# KGGR_wD.net
KiCad netlist of a schematic drawn in EAGLE
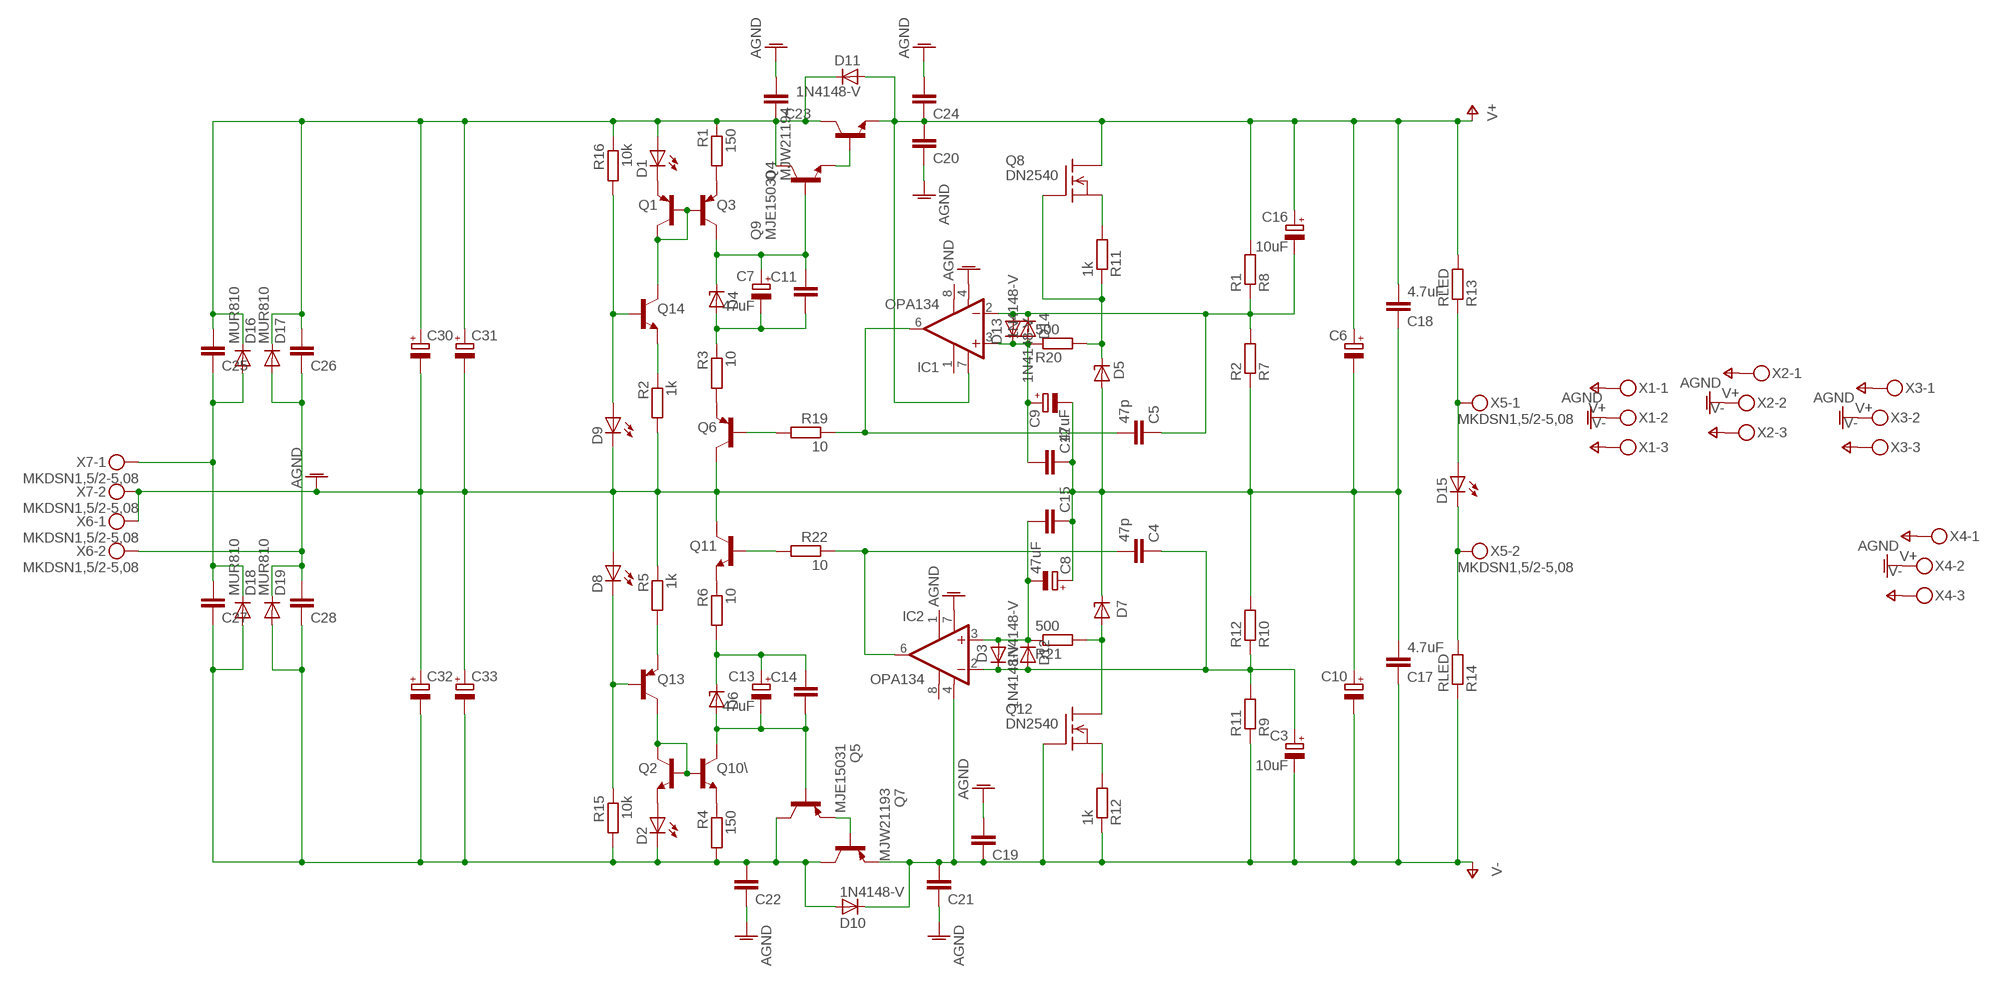
[diagram p0: schematic, sheet 1]
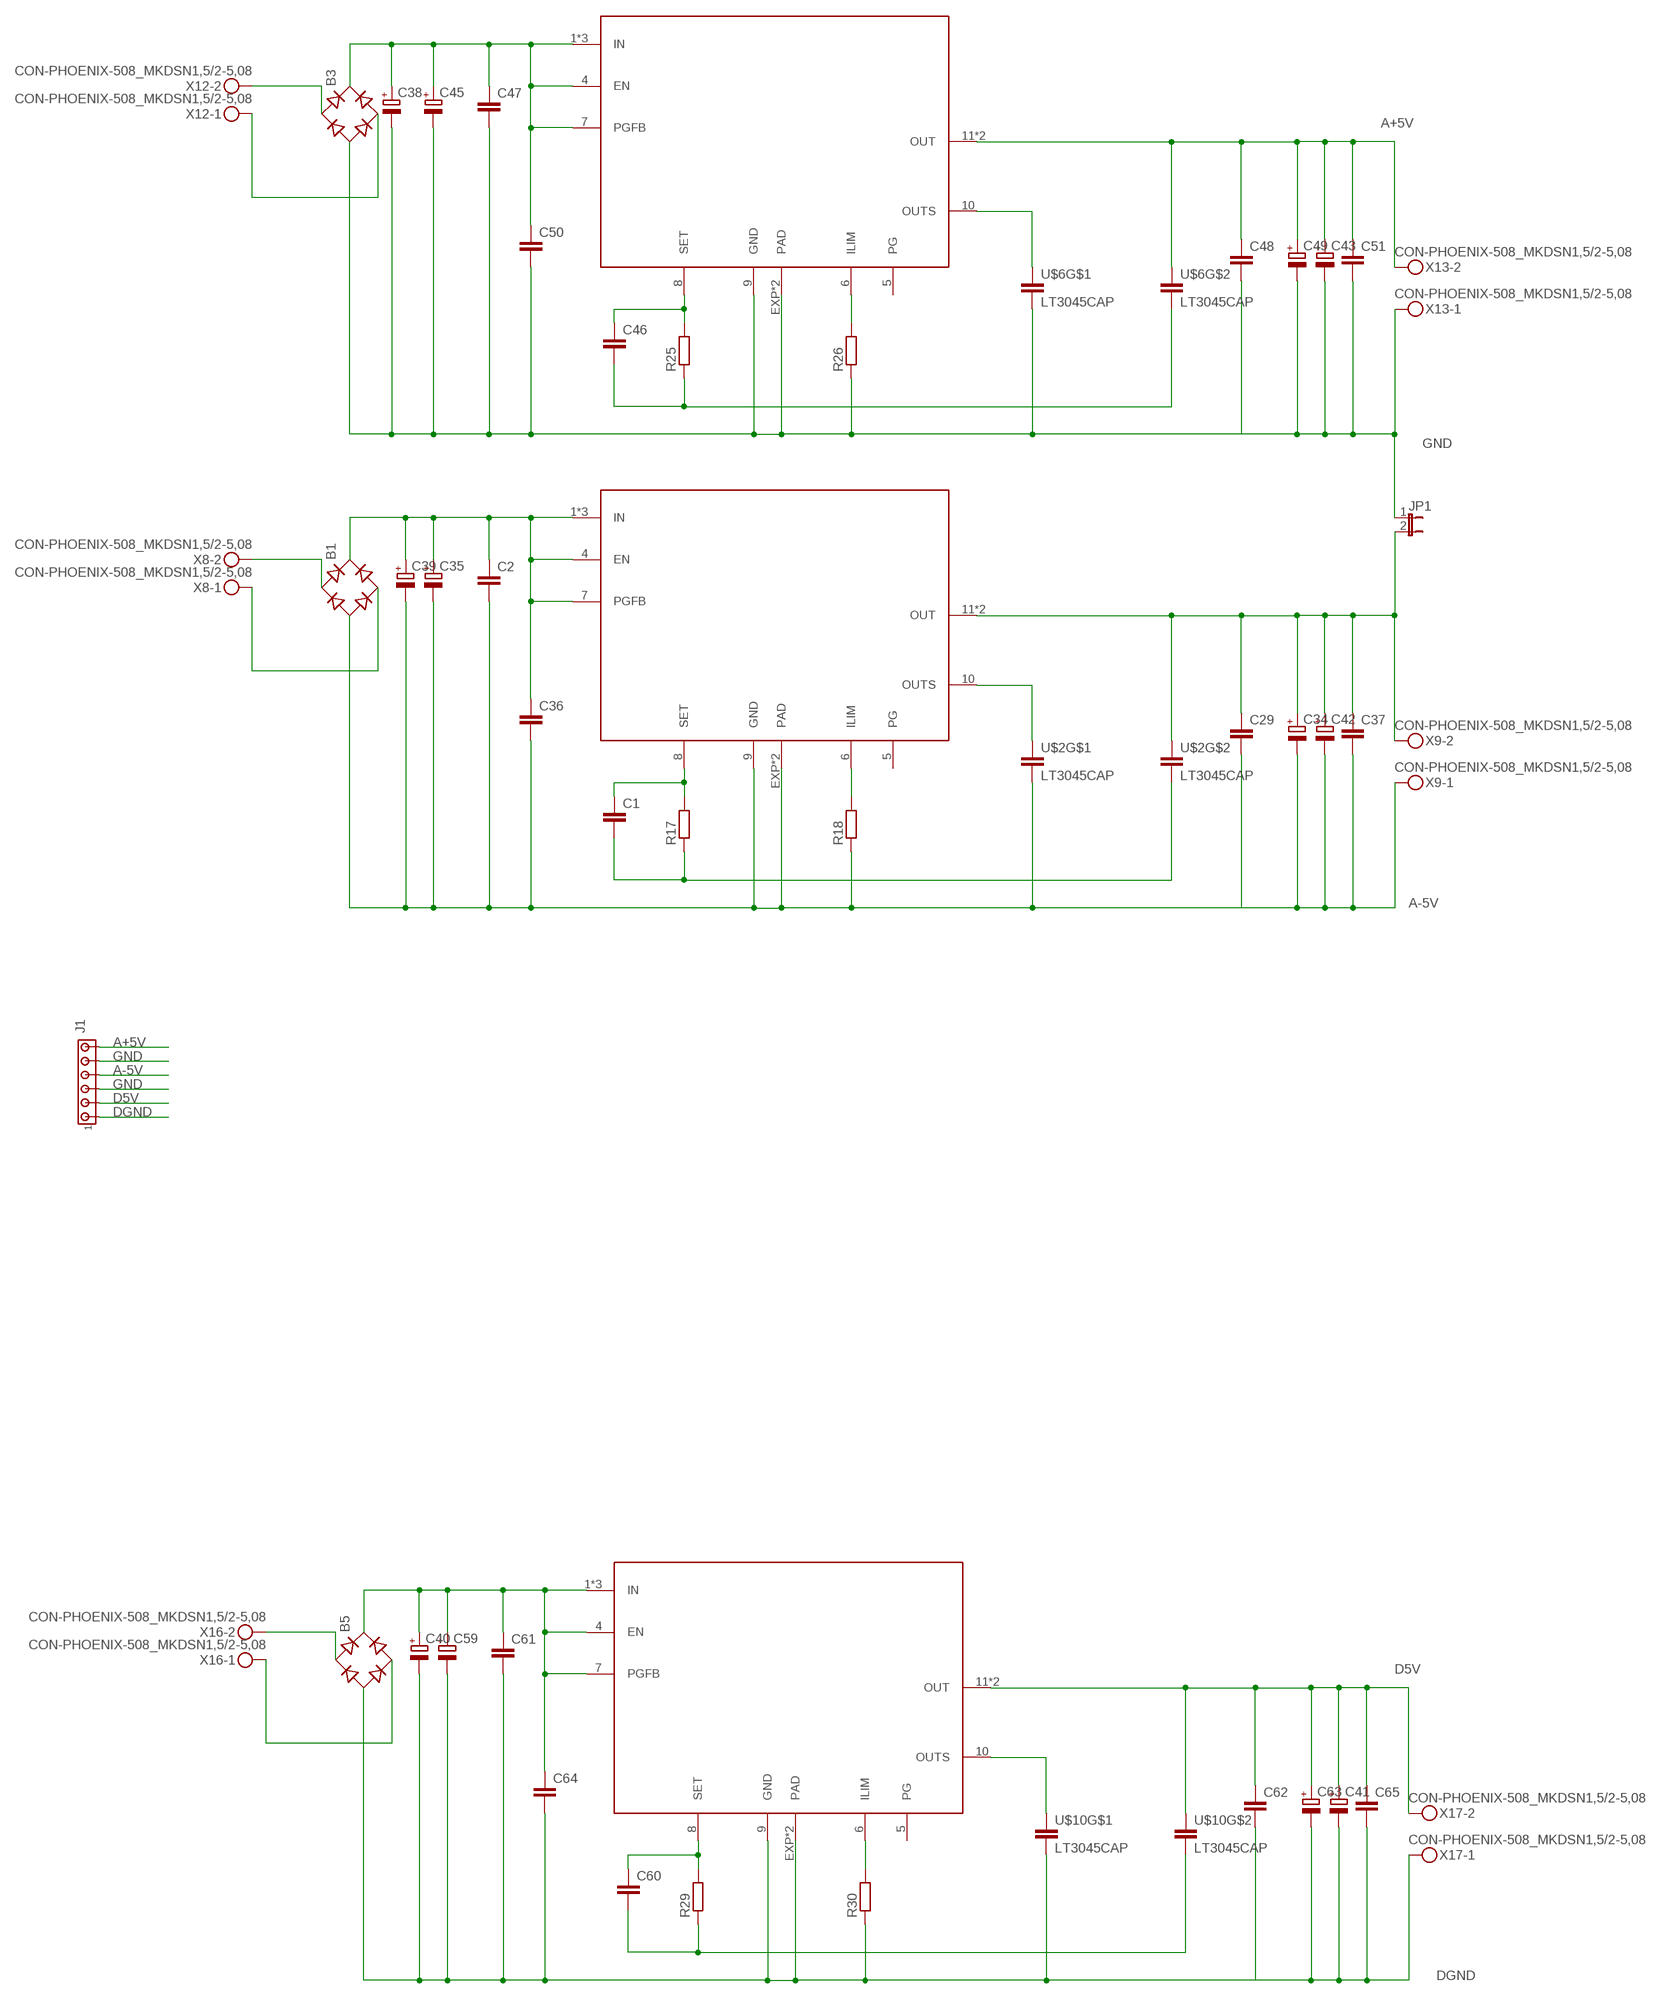
[diagram p1: schematic, sheet 2]

(export (version "E")
  (design (tool "Eeschema 10.0.6"))
  (components
    (comp (ref "B1")
      (value "RB1A")
      (footprint "eagle-import:RB1A")
      (libsource (lib "eagle-import") (part "RB1A"))
    )
    (comp (ref "B3")
      (value "RB1A")
      (footprint "eagle-import:RB1A")
      (libsource (lib "eagle-import") (part "RB1A"))
    )
    (comp (ref "B5")
      (value "RB1A")
      (footprint "eagle-import:RB1A")
      (libsource (lib "eagle-import") (part "RB1A"))
    )
    (comp (ref "C1")
      (value "C-EUC1206")
      (footprint "eagle-import:C1206")
      (libsource (lib "eagle-import") (part "C-EUC1206"))
    )
    (comp (ref "C2")
      (value "C-EU050-050X075")
      (footprint "eagle-import:C050-050X075")
      (libsource (lib "eagle-import") (part "C-EU050-050X075"))
    )
    (comp (ref "C29")
      (value "C-EU050-050X075")
      (footprint "eagle-import:C050-050X075")
      (libsource (lib "eagle-import") (part "C-EU050-050X075"))
    )
    (comp (ref "C34")
      (value "CPOL-EUE5-10.5")
      (footprint "eagle-import:E5-10,5")
      (libsource (lib "eagle-import") (part "CPOL-EUE5-10.5"))
    )
    (comp (ref "C35")
      (value "CPOL-EUE7.5-18")
      (footprint "eagle-import:E7,5-18")
      (libsource (lib "eagle-import") (part "CPOL-EUE7.5-18"))
    )
    (comp (ref "C36")
      (value "C-EUC1206")
      (footprint "eagle-import:C1206")
      (libsource (lib "eagle-import") (part "C-EUC1206"))
    )
    (comp (ref "C37")
      (value "C-EUC1206")
      (footprint "eagle-import:C1206")
      (libsource (lib "eagle-import") (part "C-EUC1206"))
    )
    (comp (ref "C38")
      (value "CPOL-EUSP-CAP-CX")
      (footprint "eagle-import:SP-CAP-CX")
      (libsource (lib "eagle-import") (part "CPOL-EUSP-CAP-CX"))
    )
    (comp (ref "C39")
      (value "CPOL-EUSP-CAP-CX")
      (footprint "eagle-import:SP-CAP-CX")
      (libsource (lib "eagle-import") (part "CPOL-EUSP-CAP-CX"))
    )
    (comp (ref "C40")
      (value "CPOL-EUSP-CAP-CX")
      (footprint "eagle-import:SP-CAP-CX")
      (libsource (lib "eagle-import") (part "CPOL-EUSP-CAP-CX"))
    )
    (comp (ref "C41")
      (value "CPOL-EUSP-CAP-CX")
      (footprint "eagle-import:SP-CAP-CX")
      (libsource (lib "eagle-import") (part "CPOL-EUSP-CAP-CX"))
    )
    (comp (ref "C42")
      (value "CPOL-EUSP-CAP-CX")
      (footprint "eagle-import:SP-CAP-CX")
      (libsource (lib "eagle-import") (part "CPOL-EUSP-CAP-CX"))
    )
    (comp (ref "C43")
      (value "CPOL-EUSP-CAP-CX")
      (footprint "eagle-import:SP-CAP-CX")
      (libsource (lib "eagle-import") (part "CPOL-EUSP-CAP-CX"))
    )
    (comp (ref "C45")
      (value "CPOL-EUE7.5-18")
      (footprint "eagle-import:E7,5-18")
      (libsource (lib "eagle-import") (part "CPOL-EUE7.5-18"))
    )
    (comp (ref "C46")
      (value "C-EUC1206")
      (footprint "eagle-import:C1206")
      (libsource (lib "eagle-import") (part "C-EUC1206"))
    )
    (comp (ref "C47")
      (value "C-EU050-050X075")
      (footprint "eagle-import:C050-050X075")
      (libsource (lib "eagle-import") (part "C-EU050-050X075"))
    )
    (comp (ref "C48")
      (value "C-EU050-050X075")
      (footprint "eagle-import:C050-050X075")
      (libsource (lib "eagle-import") (part "C-EU050-050X075"))
    )
    (comp (ref "C49")
      (value "CPOL-EUE5-10.5")
      (footprint "eagle-import:E5-10,5")
      (libsource (lib "eagle-import") (part "CPOL-EUE5-10.5"))
    )
    (comp (ref "C50")
      (value "C-EUC1206")
      (footprint "eagle-import:C1206")
      (libsource (lib "eagle-import") (part "C-EUC1206"))
    )
    (comp (ref "C51")
      (value "C-EUC1206")
      (footprint "eagle-import:C1206")
      (libsource (lib "eagle-import") (part "C-EUC1206"))
    )
    (comp (ref "C59")
      (value "CPOL-EUE7.5-18")
      (footprint "eagle-import:E7,5-18")
      (libsource (lib "eagle-import") (part "CPOL-EUE7.5-18"))
    )
    (comp (ref "C60")
      (value "C-EUC1206")
      (footprint "eagle-import:C1206")
      (libsource (lib "eagle-import") (part "C-EUC1206"))
    )
    (comp (ref "C61")
      (value "C-EU050-050X075")
      (footprint "eagle-import:C050-050X075")
      (libsource (lib "eagle-import") (part "C-EU050-050X075"))
    )
    (comp (ref "C62")
      (value "C-EU050-050X075")
      (footprint "eagle-import:C050-050X075")
      (libsource (lib "eagle-import") (part "C-EU050-050X075"))
    )
    (comp (ref "C63")
      (value "CPOL-EUE5-10.5")
      (footprint "eagle-import:E5-10,5")
      (libsource (lib "eagle-import") (part "CPOL-EUE5-10.5"))
    )
    (comp (ref "C64")
      (value "C-EUC1206")
      (footprint "eagle-import:C1206")
      (libsource (lib "eagle-import") (part "C-EUC1206"))
    )
    (comp (ref "C65")
      (value "C-EUC1206")
      (footprint "eagle-import:C1206")
      (libsource (lib "eagle-import") (part "C-EUC1206"))
    )
    (comp (ref "J1")
      (value "MTA06-156")
      (footprint "eagle-import:1X6MTA")
      (libsource (lib "eagle-import") (part "MTA06-156"))
    )
    (comp (ref "JP1")
      (value "JP1E")
      (footprint "eagle-import:JP1")
      (libsource (lib "eagle-import") (part "JP1E"))
    )
    (comp (ref "R17")
      (value "R-EU_MELF0204R")
      (footprint "eagle-import:MINI_MELF-0204R")
      (libsource (lib "eagle-import") (part "R-EU_MELF0204R"))
    )
    (comp (ref "R18")
      (value "R-EU_MELF0204R")
      (footprint "eagle-import:MINI_MELF-0204R")
      (libsource (lib "eagle-import") (part "R-EU_MELF0204R"))
    )
    (comp (ref "R25")
      (value "R-EU_MELF0204R")
      (footprint "eagle-import:MINI_MELF-0204R")
      (libsource (lib "eagle-import") (part "R-EU_MELF0204R"))
    )
    (comp (ref "R26")
      (value "R-EU_MELF0204R")
      (footprint "eagle-import:MINI_MELF-0204R")
      (libsource (lib "eagle-import") (part "R-EU_MELF0204R"))
    )
    (comp (ref "R29")
      (value "R-EU_MELF0204R")
      (footprint "eagle-import:MINI_MELF-0204R")
      (libsource (lib "eagle-import") (part "R-EU_MELF0204R"))
    )
    (comp (ref "R30")
      (value "R-EU_MELF0204R")
      (footprint "eagle-import:MINI_MELF-0204R")
      (libsource (lib "eagle-import") (part "R-EU_MELF0204R"))
    )
    (comp (ref "U$1")
      (value "LT3045")
      (footprint "eagle-import:MSOP12")
      (libsource (lib "eagle-import") (part "LT3045"))
    )
    (comp (ref "U$2")
      (value "LT3045CAP")
      (footprint "eagle-import:LT3045CAP")
      (libsource (lib "eagle-import") (part "LT3045CAP"))
    )
    (comp (ref "U$5")
      (value "LT3045")
      (footprint "eagle-import:MSOP12")
      (libsource (lib "eagle-import") (part "LT3045"))
    )
    (comp (ref "U$6")
      (value "LT3045CAP")
      (footprint "eagle-import:LT3045CAP")
      (libsource (lib "eagle-import") (part "LT3045CAP"))
    )
    (comp (ref "U$9")
      (value "LT3045")
      (footprint "eagle-import:MSOP12")
      (libsource (lib "eagle-import") (part "LT3045"))
    )
    (comp (ref "U$10")
      (value "LT3045CAP")
      (footprint "eagle-import:LT3045CAP")
      (libsource (lib "eagle-import") (part "LT3045CAP"))
    )
    (comp (ref "X8")
      (value "CON-PHOENIX-508_MKDSN1,5/2-5,08")
      (footprint "eagle-import:CON-PHOENIX-508_MKDSN1,5_2-5,08")
      (libsource (lib "eagle-import") (part "CON-PHOENIX-508_MKDSN1,5/2-5,08"))
    )
    (comp (ref "X9")
      (value "CON-PHOENIX-508_MKDSN1,5/2-5,08")
      (footprint "eagle-import:CON-PHOENIX-508_MKDSN1,5_2-5,08")
      (libsource (lib "eagle-import") (part "CON-PHOENIX-508_MKDSN1,5/2-5,08"))
    )
    (comp (ref "X12")
      (value "CON-PHOENIX-508_MKDSN1,5/2-5,08")
      (footprint "eagle-import:CON-PHOENIX-508_MKDSN1,5_2-5,08")
      (libsource (lib "eagle-import") (part "CON-PHOENIX-508_MKDSN1,5/2-5,08"))
    )
    (comp (ref "X13")
      (value "CON-PHOENIX-508_MKDSN1,5/2-5,08")
      (footprint "eagle-import:CON-PHOENIX-508_MKDSN1,5_2-5,08")
      (libsource (lib "eagle-import") (part "CON-PHOENIX-508_MKDSN1,5/2-5,08"))
    )
    (comp (ref "X16")
      (value "CON-PHOENIX-508_MKDSN1,5/2-5,08")
      (footprint "eagle-import:CON-PHOENIX-508_MKDSN1,5_2-5,08")
      (libsource (lib "eagle-import") (part "CON-PHOENIX-508_MKDSN1,5/2-5,08"))
    )
    (comp (ref "X17")
      (value "CON-PHOENIX-508_MKDSN1,5/2-5,08")
      (footprint "eagle-import:CON-PHOENIX-508_MKDSN1,5_2-5,08")
      (libsource (lib "eagle-import") (part "CON-PHOENIX-508_MKDSN1,5/2-5,08"))
    )
    (comp (ref "C3")
      (value "10uF")
      (footprint "eagle-import:E5-8,5")
      (libsource (lib "eagle-import") (part "CPOL-EUE5-8.5"))
    )
    (comp (ref "C4")
      (value "47p")
      (footprint "eagle-import:C025_050-025X075")
      (libsource (lib "eagle-import") (part "C-EU025_050-025X075"))
    )
    (comp (ref "C5")
      (value "47p")
      (footprint "eagle-import:C025_050-025X075")
      (libsource (lib "eagle-import") (part "C-EU025_050-025X075"))
    )
    (comp (ref "C6")
      (value "CPOL-EUE7.5-18")
      (footprint "eagle-import:E7,5-18")
      (libsource (lib "eagle-import") (part "CPOL-EUE7.5-18"))
    )
    (comp (ref "C7")
      (value "47uF")
      (footprint "eagle-import:E5-8,5")
      (libsource (lib "eagle-import") (part "CPOL-EUE5-8.5"))
    )
    (comp (ref "C8")
      (value "47uF")
      (footprint "eagle-import:E5-8,5")
      (libsource (lib "eagle-import") (part "CPOL-EUE5-8.5"))
    )
    (comp (ref "C9")
      (value "47uF")
      (footprint "eagle-import:E5-8,5")
      (libsource (lib "eagle-import") (part "CPOL-EUE5-8.5"))
    )
    (comp (ref "C10")
      (value "CPOL-EUE7.5-18")
      (footprint "eagle-import:E7,5-18")
      (libsource (lib "eagle-import") (part "CPOL-EUE7.5-18"))
    )
    (comp (ref "C11")
      (value "C-EU050-035X075")
      (footprint "eagle-import:C050-035X075")
      (libsource (lib "eagle-import") (part "C-EU050-035X075"))
    )
    (comp (ref "C12")
      (value "C-EU050-035X075")
      (footprint "eagle-import:C050-035X075")
      (libsource (lib "eagle-import") (part "C-EU050-035X075"))
    )
    (comp (ref "C13")
      (value "47uF")
      (footprint "eagle-import:E5-8,5")
      (libsource (lib "eagle-import") (part "CPOL-EUE5-8.5"))
    )
    (comp (ref "C14")
      (value "C-EU050-035X075")
      (footprint "eagle-import:C050-035X075")
      (libsource (lib "eagle-import") (part "C-EU050-035X075"))
    )
    (comp (ref "C15")
      (value "C-EU050-035X075")
      (footprint "eagle-import:C050-035X075")
      (libsource (lib "eagle-import") (part "C-EU050-035X075"))
    )
    (comp (ref "C16")
      (value "10uF")
      (footprint "eagle-import:E5-8,5")
      (libsource (lib "eagle-import") (part "CPOL-EUE5-8.5"))
    )
    (comp (ref "C17")
      (value "4.7uF")
      (footprint "eagle-import:C050-075X075")
      (libsource (lib "eagle-import") (part "C-EU050-075X075"))
    )
    (comp (ref "C18")
      (value "4.7uF")
      (footprint "eagle-import:C050-075X075")
      (libsource (lib "eagle-import") (part "C-EU050-075X075"))
    )
    (comp (ref "C19")
      (value "C-EU050-035X075")
      (footprint "eagle-import:C050-035X075")
      (libsource (lib "eagle-import") (part "C-EU050-035X075"))
    )
    (comp (ref "C20")
      (value "C-EU050-035X075")
      (footprint "eagle-import:C050-035X075")
      (libsource (lib "eagle-import") (part "C-EU050-035X075"))
    )
    (comp (ref "C21")
      (value "C-EU050-035X075")
      (footprint "eagle-import:C050-035X075")
      (libsource (lib "eagle-import") (part "C-EU050-035X075"))
    )
    (comp (ref "C22")
      (value "C-EU050-075X075")
      (footprint "eagle-import:C050-075X075")
      (libsource (lib "eagle-import") (part "C-EU050-075X075"))
    )
    (comp (ref "C23")
      (value "C-EU050-075X075")
      (footprint "eagle-import:C050-075X075")
      (libsource (lib "eagle-import") (part "C-EU050-075X075"))
    )
    (comp (ref "C24")
      (value "C-EU050-035X075")
      (footprint "eagle-import:C050-035X075")
      (libsource (lib "eagle-import") (part "C-EU050-035X075"))
    )
    (comp (ref "C25")
      (value "C-EU050-035X075")
      (footprint "eagle-import:C050-035X075")
      (libsource (lib "eagle-import") (part "C-EU050-035X075"))
    )
    (comp (ref "C26")
      (value "C-EU050-035X075")
      (footprint "eagle-import:C050-035X075")
      (libsource (lib "eagle-import") (part "C-EU050-035X075"))
    )
    (comp (ref "C27")
      (value "C-EU050-035X075")
      (footprint "eagle-import:C050-035X075")
      (libsource (lib "eagle-import") (part "C-EU050-035X075"))
    )
    (comp (ref "C28")
      (value "C-EU050-035X075")
      (footprint "eagle-import:C050-035X075")
      (libsource (lib "eagle-import") (part "C-EU050-035X075"))
    )
    (comp (ref "C30")
      (value "CPOL-EUE7.5-18")
      (footprint "eagle-import:E7,5-18")
      (libsource (lib "eagle-import") (part "CPOL-EUE7.5-18"))
    )
    (comp (ref "C31")
      (value "CPOL-EUE7.5-18")
      (footprint "eagle-import:E7,5-18")
      (libsource (lib "eagle-import") (part "CPOL-EUE7.5-18"))
    )
    (comp (ref "C32")
      (value "CPOL-EUE7.5-18")
      (footprint "eagle-import:E7,5-18")
      (libsource (lib "eagle-import") (part "CPOL-EUE7.5-18"))
    )
    (comp (ref "C33")
      (value "CPOL-EUE7.5-18")
      (footprint "eagle-import:E7,5-18")
      (libsource (lib "eagle-import") (part "CPOL-EUE7.5-18"))
    )
    (comp (ref "D1")
      (value "LED5MM")
      (footprint "eagle-import:LED5MM")
      (libsource (lib "eagle-import") (part "LED5MM"))
    )
    (comp (ref "D2")
      (value "LED5MM")
      (footprint "eagle-import:LED5MM")
      (libsource (lib "eagle-import") (part "LED5MM"))
    )
    (comp (ref "D3")
      (value "1N4148-V")
      (footprint "eagle-import:1N4148")
      (libsource (lib "eagle-import") (part "1N4148-V"))
    )
    (comp (ref "D4")
      (value "1N4728")
      (footprint "eagle-import:DO41Z10")
      (libsource (lib "eagle-import") (part "1N4728"))
    )
    (comp (ref "D5")
      (value "LT1021")
      (footprint "eagle-import:DIL08")
      (libsource (lib "eagle-import") (part "LT1021-V"))
    )
    (comp (ref "D6")
      (value "1N4728")
      (footprint "eagle-import:DO41Z10")
      (libsource (lib "eagle-import") (part "1N4728"))
    )
    (comp (ref "D7")
      (value "LT1021")
      (footprint "eagle-import:DIL08")
      (libsource (lib "eagle-import") (part "LT1021-V"))
    )
    (comp (ref "D8")
      (value "LED5MM")
      (footprint "eagle-import:LED5MM")
      (libsource (lib "eagle-import") (part "LED5MM"))
    )
    (comp (ref "D9")
      (value "LED5MM")
      (footprint "eagle-import:LED5MM")
      (libsource (lib "eagle-import") (part "LED5MM"))
    )
    (comp (ref "D10")
      (value "1N4148-V")
      (footprint "eagle-import:1N4148")
      (libsource (lib "eagle-import") (part "1N4148-V"))
    )
    (comp (ref "D11")
      (value "1N4148-V")
      (footprint "eagle-import:1N4148")
      (libsource (lib "eagle-import") (part "1N4148-V"))
    )
    (comp (ref "D12")
      (value "1N4148-V")
      (footprint "eagle-import:1N4148")
      (libsource (lib "eagle-import") (part "1N4148-V"))
    )
    (comp (ref "D13")
      (value "1N4148-V")
      (footprint "eagle-import:1N4148")
      (libsource (lib "eagle-import") (part "1N4148-V"))
    )
    (comp (ref "D14")
      (value "1N4148-V")
      (footprint "eagle-import:1N4148")
      (libsource (lib "eagle-import") (part "1N4148-V"))
    )
    (comp (ref "D15")
      (value "LED5MM")
      (footprint "eagle-import:LED5MM")
      (libsource (lib "eagle-import") (part "LED5MM"))
    )
    (comp (ref "D16")
      (value "MUR810")
      (footprint "eagle-import:TO220ACS")
      (libsource (lib "eagle-import") (part "MUR810"))
    )
    (comp (ref "D17")
      (value "MUR810")
      (footprint "eagle-import:TO220ACS")
      (libsource (lib "eagle-import") (part "MUR810"))
    )
    (comp (ref "D18")
      (value "MUR810")
      (footprint "eagle-import:TO220ACS")
      (libsource (lib "eagle-import") (part "MUR810"))
    )
    (comp (ref "D19")
      (value "MUR810")
      (footprint "eagle-import:TO220ACS")
      (libsource (lib "eagle-import") (part "MUR810"))
    )
    (comp (ref "IC1")
      (value "OPA134")
      (footprint "eagle-import:DIL08")
      (fields (field (name "MF") "TEXAS INSTRUMENTS") (field (name "MPN") "OPA134PA"))
      (libsource (lib "eagle-import") (part "OPA134P"))
    )
    (comp (ref "IC2")
      (value "OPA134")
      (footprint "eagle-import:DIL08")
      (fields (field (name "MF") "TEXAS INSTRUMENTS") (field (name "MPN") "OPA134PA"))
      (libsource (lib "eagle-import") (part "OPA134P"))
    )
    (comp (ref "Q1")
      (value "MPSA92-PNP-TO92-EBC")
      (footprint "eagle-import:TO92-EBC")
      (libsource (lib "eagle-import") (part "-PNP-TO92-EBCMPSA92"))
    )
    (comp (ref "Q2")
      (value "MPSA42-NPN-TO92-EBC")
      (footprint "eagle-import:TO92-EBC")
      (libsource (lib "eagle-import") (part "-NPN-TO92-EBCMPSA42"))
    )
    (comp (ref "Q3")
      (value "MPSA92-PNP-TO92-EBC")
      (footprint "eagle-import:TO92-EBC")
      (libsource (lib "eagle-import") (part "-PNP-TO92-EBCMPSA92"))
    )
    (comp (ref "Q4")
      (value "MJW21194")
      (footprint "eagle-import:TO-264")
      (libsource (lib "eagle-import") (part "MJL4281"))
    )
    (comp (ref "Q5")
      (value "MJE15031")
      (footprint "eagle-import:TO220KG")
      (libsource (lib "eagle-import") (part "MJE15031"))
    )
    (comp (ref "Q6")
      (value "MPSA92-PNP-TO92-EBC")
      (footprint "eagle-import:TO92-EBC")
      (libsource (lib "eagle-import") (part "-PNP-TO92-EBCMPSA92"))
    )
    (comp (ref "Q7")
      (value "MJW21193")
      (footprint "eagle-import:TO-264")
      (libsource (lib "eagle-import") (part "MJL4302"))
    )
    (comp (ref "Q8")
      (value "DN2540")
      (footprint "eagle-import:TO92-")
      (libsource (lib "eagle-import") (part "2N7000"))
    )
    (comp (ref "Q9")
      (value "MJE15030")
      (footprint "eagle-import:TO220KG")
      (libsource (lib "eagle-import") (part "MJE15030"))
    )
    (comp (ref "Q10\\")
      (value "MPSA42-NPN-TO92-EBC")
      (footprint "eagle-import:TO92-EBC")
      (libsource (lib "eagle-import") (part "-NPN-TO92-EBCMPSA42"))
    )
    (comp (ref "Q11")
      (value "MPSA42-NPN-TO92-EBC")
      (footprint "eagle-import:TO92-EBC")
      (libsource (lib "eagle-import") (part "-NPN-TO92-EBCMPSA42"))
    )
    (comp (ref "Q12")
      (value "DN2540")
      (footprint "eagle-import:TO92-")
      (libsource (lib "eagle-import") (part "2N7000"))
    )
    (comp (ref "Q13")
      (value "MPSA92-PNP-TO92-EBC")
      (footprint "eagle-import:TO92-EBC")
      (libsource (lib "eagle-import") (part "-PNP-TO92-EBCMPSA92"))
    )
    (comp (ref "Q14")
      (value "MPSA42-NPN-TO92-EBC")
      (footprint "eagle-import:TO92-EBC")
      (libsource (lib "eagle-import") (part "-NPN-TO92-EBCMPSA42"))
    )
    (comp (ref "R1")
      (value "150")
      (footprint "eagle-import:0309_12")
      (libsource (lib "eagle-import") (part "R-EU_0309/12"))
    )
    (comp (ref "R2")
      (value "1k")
      (footprint "eagle-import:0309_12")
      (libsource (lib "eagle-import") (part "R-EU_0309/12"))
    )
    (comp (ref "R3")
      (value "10")
      (footprint "eagle-import:0309_12")
      (libsource (lib "eagle-import") (part "R-EU_0309/12"))
    )
    (comp (ref "R4")
      (value "150")
      (footprint "eagle-import:0309_12")
      (libsource (lib "eagle-import") (part "R-EU_0309/12"))
    )
    (comp (ref "R5")
      (value "1k")
      (footprint "eagle-import:0309_12")
      (libsource (lib "eagle-import") (part "R-EU_0309/12"))
    )
    (comp (ref "R6")
      (value "10")
      (footprint "eagle-import:0309_12")
      (libsource (lib "eagle-import") (part "R-EU_0309/12"))
    )
    (comp (ref "R7")
      (value "R2")
      (footprint "eagle-import:0309_12")
      (libsource (lib "eagle-import") (part "R-EU_0309/12"))
    )
    (comp (ref "R8")
      (value "R1")
      (footprint "eagle-import:0309_12")
      (libsource (lib "eagle-import") (part "R-EU_0309/12"))
    )
    (comp (ref "R9")
      (value "R11")
      (footprint "eagle-import:0309_12")
      (libsource (lib "eagle-import") (part "R-EU_0309/12"))
    )
    (comp (ref "R10")
      (value "R12")
      (footprint "eagle-import:0309_12")
      (libsource (lib "eagle-import") (part "R-EU_0309/12"))
    )
    (comp (ref "R11")
      (value "1k")
      (footprint "eagle-import:0309_12")
      (libsource (lib "eagle-import") (part "R-EU_0309/12"))
    )
    (comp (ref "R12")
      (value "1k")
      (footprint "eagle-import:0309_12")
      (libsource (lib "eagle-import") (part "R-EU_0309/12"))
    )
    (comp (ref "R13")
      (value "RLED")
      (footprint "eagle-import:0309_12")
      (libsource (lib "eagle-import") (part "R-EU_0309/12"))
    )
    (comp (ref "R14")
      (value "RLED")
      (footprint "eagle-import:0309_12")
      (libsource (lib "eagle-import") (part "R-EU_0309/12"))
    )
    (comp (ref "R15")
      (value "10k")
      (footprint "eagle-import:0309_12")
      (libsource (lib "eagle-import") (part "R-EU_0309/12"))
    )
    (comp (ref "R16")
      (value "10k")
      (footprint "eagle-import:0309_12")
      (libsource (lib "eagle-import") (part "R-EU_0309/12"))
    )
    (comp (ref "R19")
      (value "10")
      (footprint "eagle-import:0309_12")
      (libsource (lib "eagle-import") (part "R-EU_0309/12"))
    )
    (comp (ref "R20")
      (value "500")
      (footprint "eagle-import:0309_12")
      (libsource (lib "eagle-import") (part "R-EU_0309/12"))
    )
    (comp (ref "R21")
      (value "500")
      (footprint "eagle-import:0309_12")
      (libsource (lib "eagle-import") (part "R-EU_0309/12"))
    )
    (comp (ref "R22")
      (value "10")
      (footprint "eagle-import:0309_12")
      (libsource (lib "eagle-import") (part "R-EU_0309/12"))
    )
    (comp (ref "X1")
      (value "MKDSN1,5/3-5,08")
      (footprint "eagle-import:MKDSN1,5_3-5,08")
      (libsource (lib "eagle-import") (part "MKDSN1,5/3-5,08"))
    )
    (comp (ref "X2")
      (value "MKDSN1,5/3-5,08")
      (footprint "eagle-import:MKDSN1,5_3-5,08")
      (libsource (lib "eagle-import") (part "MKDSN1,5/3-5,08"))
    )
    (comp (ref "X3")
      (value "MKDSN1,5/3-5,08")
      (footprint "eagle-import:MKDSN1,5_3-5,08")
      (libsource (lib "eagle-import") (part "MKDSN1,5/3-5,08"))
    )
    (comp (ref "X4")
      (value "MKDSN1,5/3-5,08")
      (footprint "eagle-import:MKDSN1,5_3-5,08")
      (libsource (lib "eagle-import") (part "MKDSN1,5/3-5,08"))
    )
    (comp (ref "X5")
      (value "MKDSN1,5/2-5,08")
      (footprint "eagle-import:MKDSN1,5_2-5,08")
      (libsource (lib "eagle-import") (part "MKDSN1,5/2-5,08"))
    )
    (comp (ref "X6")
      (value "MKDSN1,5/2-5,08")
      (footprint "eagle-import:MKDSN1,5_2-5,08")
      (libsource (lib "eagle-import") (part "MKDSN1,5/2-5,08"))
    )
    (comp (ref "X7")
      (value "MKDSN1,5/2-5,08")
      (footprint "eagle-import:MKDSN1,5_2-5,08")
      (libsource (lib "eagle-import") (part "MKDSN1,5/2-5,08"))
    )
  )
  (nets
    (net (code "1") (name "A+5V") (class "Default")
      (node (ref "C43") (pin "+") (pinfunction "+_+") (pintype "passive"))
      (node (ref "C48") (pin "1") (pinfunction "1_1") (pintype "passive"))
      (node (ref "C49") (pin "+") (pinfunction "+_+") (pintype "passive"))
      (node (ref "C51") (pin "1") (pinfunction "1_1") (pintype "passive"))
      (node (ref "J1") (pin "6") (pinfunction "6_6") (pintype "passive"))
      (node (ref "U$5") (pin "11") (pinfunction "OUT_11") (pintype "bidirectional"))
      (node (ref "U$5") (pin "12") (pinfunction "OUT_12") (pintype "bidirectional"))
      (node (ref "U$6") (pin "4") (pinfunction "1_4") (pintype "passive"))
      (node (ref "X13") (pin "2") (pinfunction "KL_2") (pintype "passive"))
    )
    (net (code "2") (name "A-5V") (class "Default")
      (node (ref "B1") (pin "-") (pinfunction "-_-") (pintype "passive"))
      (node (ref "C2") (pin "2") (pinfunction "2_2") (pintype "passive"))
      (node (ref "C29") (pin "2") (pinfunction "2_2") (pintype "passive"))
      (node (ref "C34") (pin "-") (pinfunction "-_-") (pintype "passive"))
      (node (ref "C35") (pin "-") (pinfunction "-_-") (pintype "passive"))
      (node (ref "C36") (pin "2") (pinfunction "2_2") (pintype "passive"))
      (node (ref "C37") (pin "2") (pinfunction "2_2") (pintype "passive"))
      (node (ref "C39") (pin "-") (pinfunction "-_-") (pintype "passive"))
      (node (ref "C42") (pin "-") (pinfunction "-_-") (pintype "passive"))
      (node (ref "J1") (pin "4") (pinfunction "4_4") (pintype "passive"))
      (node (ref "R18") (pin "1") (pinfunction "1_1") (pintype "passive"))
      (node (ref "U$1") (pin "9") (pinfunction "GND_9") (pintype "bidirectional"))
      (node (ref "U$1") (pin "EXP") (pinfunction "PAD_EXP") (pintype "bidirectional"))
      (node (ref "U$1") (pin "EXP1") (pinfunction "PAD_EXP1") (pintype "bidirectional"))
      (node (ref "U$2") (pin "5") (pinfunction "2_5") (pintype "passive"))
      (node (ref "X9") (pin "1") (pinfunction "KL_1") (pintype "passive"))
    )
    (net (code "3") (name "AGND") (class "Default")
      (node (ref "C10") (pin "+") (pinfunction "+_+") (pintype "passive"))
      (node (ref "C12") (pin "1") (pinfunction "1_1") (pintype "passive"))
      (node (ref "C15") (pin "1") (pinfunction "1_1") (pintype "passive"))
      (node (ref "C17") (pin "2") (pinfunction "2_2") (pintype "passive"))
      (node (ref "C18") (pin "1") (pinfunction "1_1") (pintype "passive"))
      (node (ref "C19") (pin "2") (pinfunction "2_2") (pintype "passive"))
      (node (ref "C20") (pin "1") (pinfunction "1_1") (pintype "passive"))
      (node (ref "C21") (pin "1") (pinfunction "1_1") (pintype "passive"))
      (node (ref "C22") (pin "1") (pinfunction "1_1") (pintype "passive"))
      (node (ref "C23") (pin "2") (pinfunction "2_2") (pintype "passive"))
      (node (ref "C24") (pin "2") (pinfunction "2_2") (pintype "passive"))
      (node (ref "C30") (pin "-") (pinfunction "-_-") (pintype "passive"))
      (node (ref "C31") (pin "-") (pinfunction "-_-") (pintype "passive"))
      (node (ref "C32") (pin "+") (pinfunction "+_+") (pintype "passive"))
      (node (ref "C33") (pin "+") (pinfunction "+_+") (pintype "passive"))
      (node (ref "C6") (pin "-") (pinfunction "-_-") (pintype "passive"))
      (node (ref "C8") (pin "+") (pinfunction "+_+") (pintype "passive"))
      (node (ref "C9") (pin "-") (pinfunction "-_-") (pintype "passive"))
      (node (ref "D5") (pin "4") (pinfunction "GND_4") (pintype "passive"))
      (node (ref "D7") (pin "6") (pinfunction "OUT_6") (pintype "passive"))
      (node (ref "D8") (pin "A") (pinfunction "A_A") (pintype "passive"))
      (node (ref "D9") (pin "K") (pinfunction "C_K") (pintype "passive"))
      (node (ref "IC1") (pin "4") (pinfunction "V-_4") (pintype "power_in"))
      (node (ref "IC2") (pin "7") (pinfunction "V+_7") (pintype "power_in"))
      (node (ref "Q11") (pin "C") (pinfunction "C_C") (pintype "passive"))
      (node (ref "Q6") (pin "C") (pinfunction "C_C") (pintype "passive"))
      (node (ref "R10") (pin "2") (pinfunction "2_2") (pintype "passive"))
      (node (ref "R2") (pin "2") (pinfunction "2_2") (pintype "passive"))
      (node (ref "R5") (pin "1") (pinfunction "1_1") (pintype "passive"))
      (node (ref "R7") (pin "1") (pinfunction "1_1") (pintype "passive"))
      (node (ref "X1") (pin "2") (pinfunction "KL_2") (pintype "passive"))
      (node (ref "X2") (pin "2") (pinfunction "KL_2") (pintype "passive"))
      (node (ref "X3") (pin "2") (pinfunction "KL_2") (pintype "passive"))
      (node (ref "X4") (pin "2") (pinfunction "KL_2") (pintype "passive"))
      (node (ref "X6") (pin "1") (pinfunction "KL_1") (pintype "passive"))
      (node (ref "X7") (pin "2") (pinfunction "KL_2") (pintype "passive"))
    )
    (net (code "4") (name "D5V") (class "Default")
      (node (ref "C41") (pin "+") (pinfunction "+_+") (pintype "passive"))
      (node (ref "C62") (pin "1") (pinfunction "1_1") (pintype "passive"))
      (node (ref "C63") (pin "+") (pinfunction "+_+") (pintype "passive"))
      (node (ref "C65") (pin "1") (pinfunction "1_1") (pintype "passive"))
      (node (ref "J1") (pin "2") (pinfunction "2_2") (pintype "passive"))
      (node (ref "U$10") (pin "4") (pinfunction "1_4") (pintype "passive"))
      (node (ref "U$9") (pin "11") (pinfunction "OUT_11") (pintype "bidirectional"))
      (node (ref "U$9") (pin "12") (pinfunction "OUT_12") (pintype "bidirectional"))
      (node (ref "X17") (pin "2") (pinfunction "KL_2") (pintype "passive"))
    )
    (net (code "5") (name "DGND") (class "Default")
      (node (ref "B5") (pin "-") (pinfunction "-_-") (pintype "passive"))
      (node (ref "C40") (pin "-") (pinfunction "-_-") (pintype "passive"))
      (node (ref "C41") (pin "-") (pinfunction "-_-") (pintype "passive"))
      (node (ref "C59") (pin "-") (pinfunction "-_-") (pintype "passive"))
      (node (ref "C61") (pin "2") (pinfunction "2_2") (pintype "passive"))
      (node (ref "C62") (pin "2") (pinfunction "2_2") (pintype "passive"))
      (node (ref "C63") (pin "-") (pinfunction "-_-") (pintype "passive"))
      (node (ref "C64") (pin "2") (pinfunction "2_2") (pintype "passive"))
      (node (ref "C65") (pin "2") (pinfunction "2_2") (pintype "passive"))
      (node (ref "J1") (pin "1") (pinfunction "1_1") (pintype "passive"))
      (node (ref "R30") (pin "1") (pinfunction "1_1") (pintype "passive"))
      (node (ref "U$10") (pin "5") (pinfunction "2_5") (pintype "passive"))
      (node (ref "U$9") (pin "9") (pinfunction "GND_9") (pintype "bidirectional"))
      (node (ref "U$9") (pin "EXP") (pinfunction "PAD_EXP") (pintype "bidirectional"))
      (node (ref "U$9") (pin "EXP1") (pinfunction "PAD_EXP1") (pintype "bidirectional"))
      (node (ref "X17") (pin "1") (pinfunction "KL_1") (pintype "passive"))
    )
    (net (code "6") (name "GND") (class "Default")
      (node (ref "B3") (pin "-") (pinfunction "-_-") (pintype "passive"))
      (node (ref "C38") (pin "-") (pinfunction "-_-") (pintype "passive"))
      (node (ref "C43") (pin "-") (pinfunction "-_-") (pintype "passive"))
      (node (ref "C45") (pin "-") (pinfunction "-_-") (pintype "passive"))
      (node (ref "C47") (pin "2") (pinfunction "2_2") (pintype "passive"))
      (node (ref "C48") (pin "2") (pinfunction "2_2") (pintype "passive"))
      (node (ref "C49") (pin "-") (pinfunction "-_-") (pintype "passive"))
      (node (ref "C50") (pin "2") (pinfunction "2_2") (pintype "passive"))
      (node (ref "C51") (pin "2") (pinfunction "2_2") (pintype "passive"))
      (node (ref "J1") (pin "3") (pinfunction "3_3") (pintype "passive"))
      (node (ref "J1") (pin "5") (pinfunction "5_5") (pintype "passive"))
      (node (ref "JP1") (pin "1") (pinfunction "1_1") (pintype "passive"))
      (node (ref "R26") (pin "1") (pinfunction "1_1") (pintype "passive"))
      (node (ref "U$5") (pin "9") (pinfunction "GND_9") (pintype "bidirectional"))
      (node (ref "U$5") (pin "EXP") (pinfunction "PAD_EXP") (pintype "bidirectional"))
      (node (ref "U$5") (pin "EXP1") (pinfunction "PAD_EXP1") (pintype "bidirectional"))
      (node (ref "U$6") (pin "5") (pinfunction "2_5") (pintype "passive"))
      (node (ref "X13") (pin "1") (pinfunction "KL_1") (pintype "passive"))
    )
    (net (code "7") (name "Net-(C11-Pad2)") (class "Default")
      (node (ref "C11") (pin "2") (pinfunction "2_2") (pintype "passive"))
      (node (ref "C7") (pin "-") (pinfunction "-_-") (pintype "passive"))
      (node (ref "D4") (pin "A") (pinfunction "A_A") (pintype "passive"))
      (node (ref "R3") (pin "1") (pinfunction "1_1") (pintype "passive"))
    )
    (net (code "8") (name "Net-(C13-Pad+)") (class "Default")
      (node (ref "C13") (pin "+") (pinfunction "+_+") (pintype "passive"))
      (node (ref "C14") (pin "1") (pinfunction "1_1") (pintype "passive"))
      (node (ref "D6") (pin "C") (pinfunction "C_C") (pintype "passive"))
      (node (ref "R6") (pin "2") (pinfunction "2_2") (pintype "passive"))
    )
    (net (code "9") (name "Net-(D1-C)") (class "Default")
      (node (ref "D1") (pin "K") (pinfunction "C_K") (pintype "passive"))
      (node (ref "Q1") (pin "E") (pinfunction "E_E") (pintype "passive"))
    )
    (net (code "10") (name "Net-(D2-C)") (class "Default")
      (node (ref "C22") (pin "2") (pinfunction "2_2") (pintype "passive"))
      (node (ref "C27") (pin "1") (pinfunction "1_1") (pintype "passive"))
      (node (ref "C28") (pin "1") (pinfunction "1_1") (pintype "passive"))
      (node (ref "C32") (pin "-") (pinfunction "-_-") (pintype "passive"))
      (node (ref "C33") (pin "-") (pinfunction "-_-") (pintype "passive"))
      (node (ref "D10") (pin "A") (pinfunction "A_A") (pintype "passive"))
      (node (ref "D18") (pin "A") (pinfunction "A_A") (pintype "passive"))
      (node (ref "D19") (pin "A") (pinfunction "A_A") (pintype "passive"))
      (node (ref "D2") (pin "K") (pinfunction "C_K") (pintype "passive"))
      (node (ref "Q5") (pin "2") (pinfunction "C_2") (pintype "passive"))
      (node (ref "Q7") (pin "C") (pinfunction "C_C") (pintype "passive"))
      (node (ref "R15") (pin "2") (pinfunction "2_2") (pintype "passive"))
      (node (ref "R4") (pin "2") (pinfunction "2_2") (pintype "passive"))
    )
    (net (code "11") (name "Net-(D2-PadA)") (class "Default")
      (node (ref "D2") (pin "A") (pinfunction "A_A") (pintype "passive"))
      (node (ref "Q2") (pin "E") (pinfunction "E_E") (pintype "passive"))
    )
    (net (code "12") (name "Net-(D5-OUT)") (class "Default")
      (node (ref "D5") (pin "6") (pinfunction "OUT_6") (pintype "passive"))
      (node (ref "Q8") (pin "2") (pinfunction "G_2") (pintype "passive"))
      (node (ref "R11") (pin "1") (pinfunction "1_1") (pintype "passive"))
      (node (ref "R20") (pin "2") (pinfunction "2_2") (pintype "passive"))
    )
    (net (code "13") (name "Net-(D7-GND)") (class "Default")
      (node (ref "D7") (pin "4") (pinfunction "GND_4") (pintype "passive"))
      (node (ref "Q12") (pin "1") (pinfunction "D_1") (pintype "passive"))
      (node (ref "R21") (pin "2") (pinfunction "2_2") (pintype "passive"))
    )
    (net (code "14") (name "Net-(D8-C)") (class "Default")
      (node (ref "D8") (pin "K") (pinfunction "C_K") (pintype "passive"))
      (node (ref "Q13") (pin "B") (pinfunction "B_B") (pintype "passive"))
      (node (ref "R15") (pin "1") (pinfunction "1_1") (pintype "passive"))
    )
    (net (code "15") (name "Net-(D9-PadA)") (class "Default")
      (node (ref "D9") (pin "A") (pinfunction "A_A") (pintype "passive"))
      (node (ref "Q14") (pin "B") (pinfunction "B_B") (pintype "passive"))
      (node (ref "R16") (pin "2") (pinfunction "2_2") (pintype "passive"))
    )
    (net (code "16") (name "Net-(D15-C)") (class "Default")
      (node (ref "D15") (pin "K") (pinfunction "C_K") (pintype "passive"))
      (node (ref "R14") (pin "2") (pinfunction "2_2") (pintype "passive"))
      (node (ref "X5") (pin "2") (pinfunction "KL_2") (pintype "passive"))
    )
    (net (code "17") (name "Net-(IC1-+IN)") (class "Default")
      (node (ref "C12") (pin "2") (pinfunction "2_2") (pintype "passive"))
      (node (ref "C9") (pin "+") (pinfunction "+_+") (pintype "passive"))
      (node (ref "D13") (pin "C") (pinfunction "C_C") (pintype "passive"))
      (node (ref "D14") (pin "A") (pinfunction "A_A") (pintype "passive"))
      (node (ref "IC1") (pin "3") (pinfunction "+IN_3") (pintype "input"))
      (node (ref "R20") (pin "1") (pinfunction "1_1") (pintype "passive"))
    )
    (net (code "18") (name "Net-(IC1--IN)") (class "Default")
      (node (ref "C16") (pin "-") (pinfunction "-_-") (pintype "passive"))
      (node (ref "C5") (pin "1") (pinfunction "1_1") (pintype "passive"))
      (node (ref "D13") (pin "A") (pinfunction "A_A") (pintype "passive"))
      (node (ref "D14") (pin "C") (pinfunction "C_C") (pintype "passive"))
      (node (ref "IC1") (pin "2") (pinfunction "-IN_2") (pintype "input"))
      (node (ref "R7") (pin "2") (pinfunction "2_2") (pintype "passive"))
      (node (ref "R8") (pin "1") (pinfunction "1_1") (pintype "passive"))
    )
    (net (code "19") (name "Net-(IC1-OUT)") (class "Default")
      (node (ref "C5") (pin "2") (pinfunction "2_2") (pintype "passive"))
      (node (ref "C5") (pin "3") (pinfunction "2_3") (pintype "passive"))
      (node (ref "IC1") (pin "6") (pinfunction "OUT_6") (pintype "output"))
      (node (ref "R19") (pin "1") (pinfunction "1_1") (pintype "passive"))
    )
    (net (code "20") (name "Net-(IC2-+IN)") (class "Default")
      (node (ref "C15") (pin "2") (pinfunction "2_2") (pintype "passive"))
      (node (ref "C8") (pin "-") (pinfunction "-_-") (pintype "passive"))
      (node (ref "D12") (pin "C") (pinfunction "C_C") (pintype "passive"))
      (node (ref "D3") (pin "A") (pinfunction "A_A") (pintype "passive"))
      (node (ref "IC2") (pin "3") (pinfunction "+IN_3") (pintype "input"))
      (node (ref "R21") (pin "1") (pinfunction "1_1") (pintype "passive"))
    )
    (net (code "21") (name "Net-(IC2--IN)") (class "Default")
      (node (ref "C3") (pin "+") (pinfunction "+_+") (pintype "passive"))
      (node (ref "C4") (pin "1") (pinfunction "1_1") (pintype "passive"))
      (node (ref "D12") (pin "A") (pinfunction "A_A") (pintype "passive"))
      (node (ref "D3") (pin "C") (pinfunction "C_C") (pintype "passive"))
      (node (ref "IC2") (pin "2") (pinfunction "-IN_2") (pintype "input"))
      (node (ref "R10") (pin "1") (pinfunction "1_1") (pintype "passive"))
      (node (ref "R9") (pin "2") (pinfunction "2_2") (pintype "passive"))
    )
    (net (code "22") (name "Net-(IC2-OUT)") (class "Default")
      (node (ref "C4") (pin "2") (pinfunction "2_2") (pintype "passive"))
      (node (ref "C4") (pin "3") (pinfunction "2_3") (pintype "passive"))
      (node (ref "IC2") (pin "6") (pinfunction "OUT_6") (pintype "output"))
      (node (ref "R22") (pin "1") (pinfunction "1_1") (pintype "passive"))
    )
    (net (code "23") (name "Net-(Q1-PadB)") (class "Default")
      (node (ref "Q1") (pin "B") (pinfunction "B_B") (pintype "passive"))
      (node (ref "Q1") (pin "C") (pinfunction "C_C") (pintype "passive"))
      (node (ref "Q14") (pin "C") (pinfunction "C_C") (pintype "passive"))
      (node (ref "Q3") (pin "B") (pinfunction "B_B") (pintype "passive"))
    )
    (net (code "24") (name "Net-(Q3-PadE)") (class "Default")
      (node (ref "Q3") (pin "E") (pinfunction "E_E") (pintype "passive"))
      (node (ref "R1") (pin "2") (pinfunction "2_2") (pintype "passive"))
    )
    (net (code "25") (name "Net-(Q5-B)") (class "Default")
      (node (ref "C13") (pin "-") (pinfunction "-_-") (pintype "passive"))
      (node (ref "C14") (pin "2") (pinfunction "2_2") (pintype "passive"))
      (node (ref "D6") (pin "A") (pinfunction "A_A") (pintype "passive"))
      (node (ref "Q10\\") (pin "C") (pinfunction "C_C") (pintype "passive"))
      (node (ref "Q5") (pin "1") (pinfunction "B_1") (pintype "passive"))
    )
    (net (code "26") (name "Net-(Q5-E)") (class "Default")
      (node (ref "Q5") (pin "3") (pinfunction "E_3") (pintype "passive"))
      (node (ref "Q7") (pin "B") (pinfunction "B_B") (pintype "passive"))
    )
    (net (code "27") (name "Net-(Q6-PadB)") (class "Default")
      (node (ref "Q6") (pin "B") (pinfunction "B_B") (pintype "passive"))
      (node (ref "R19") (pin "2") (pinfunction "2_2") (pintype "passive"))
    )
    (net (code "28") (name "Net-(Q6-PadE)") (class "Default")
      (node (ref "Q6") (pin "E") (pinfunction "E_E") (pintype "passive"))
      (node (ref "R3") (pin "2") (pinfunction "2_2") (pintype "passive"))
    )
    (net (code "29") (name "Net-(Q8-S)") (class "Default")
      (node (ref "Q8") (pin "3") (pinfunction "S_3") (pintype "passive"))
      (node (ref "R11") (pin "2") (pinfunction "2_2") (pintype "passive"))
    )
    (net (code "30") (name "Net-(Q9-B)") (class "Default")
      (node (ref "C11") (pin "1") (pinfunction "1_1") (pintype "passive"))
      (node (ref "C7") (pin "+") (pinfunction "+_+") (pintype "passive"))
      (node (ref "D4") (pin "C") (pinfunction "C_C") (pintype "passive"))
      (node (ref "Q3") (pin "C") (pinfunction "C_C") (pintype "passive"))
      (node (ref "Q9") (pin "1") (pinfunction "B_1") (pintype "passive"))
    )
    (net (code "31") (name "Net-(Q9-C)") (class "Default")
      (node (ref "C23") (pin "1") (pinfunction "1_1") (pintype "passive"))
      (node (ref "C25") (pin "2") (pinfunction "2_2") (pintype "passive"))
      (node (ref "C26") (pin "2") (pinfunction "2_2") (pintype "passive"))
      (node (ref "C30") (pin "+") (pinfunction "+_+") (pintype "passive"))
      (node (ref "C31") (pin "+") (pinfunction "+_+") (pintype "passive"))
      (node (ref "D1") (pin "A") (pinfunction "A_A") (pintype "passive"))
      (node (ref "D11") (pin "C") (pinfunction "C_C") (pintype "passive"))
      (node (ref "D16") (pin "C") (pinfunction "C_C") (pintype "passive"))
      (node (ref "D17") (pin "C") (pinfunction "C_C") (pintype "passive"))
      (node (ref "Q4") (pin "C") (pinfunction "C_C") (pintype "passive"))
      (node (ref "Q9") (pin "2") (pinfunction "C_2") (pintype "passive"))
      (node (ref "R1") (pin "1") (pinfunction "1_1") (pintype "passive"))
      (node (ref "R16") (pin "1") (pinfunction "1_1") (pintype "passive"))
    )
    (net (code "32") (name "Net-(Q9-E)") (class "Default")
      (node (ref "Q4") (pin "B") (pinfunction "B_B") (pintype "passive"))
      (node (ref "Q9") (pin "3") (pinfunction "E_3") (pintype "passive"))
    )
    (net (code "33") (name "Net-(Q10\\-PadB)") (class "Default")
      (node (ref "Q10\\") (pin "B") (pinfunction "B_B") (pintype "passive"))
      (node (ref "Q13") (pin "C") (pinfunction "C_C") (pintype "passive"))
      (node (ref "Q2") (pin "B") (pinfunction "B_B") (pintype "passive"))
      (node (ref "Q2") (pin "C") (pinfunction "C_C") (pintype "passive"))
    )
    (net (code "34") (name "Net-(Q10\\-PadE)") (class "Default")
      (node (ref "Q10\\") (pin "E") (pinfunction "E_E") (pintype "passive"))
      (node (ref "R4") (pin "1") (pinfunction "1_1") (pintype "passive"))
    )
    (net (code "35") (name "Net-(Q11-PadB)") (class "Default")
      (node (ref "Q11") (pin "B") (pinfunction "B_B") (pintype "passive"))
      (node (ref "R22") (pin "2") (pinfunction "2_2") (pintype "passive"))
    )
    (net (code "36") (name "Net-(Q11-PadE)") (class "Default")
      (node (ref "Q11") (pin "E") (pinfunction "E_E") (pintype "passive"))
      (node (ref "R6") (pin "1") (pinfunction "1_1") (pintype "passive"))
    )
    (net (code "37") (name "Net-(Q12-S)") (class "Default")
      (node (ref "Q12") (pin "3") (pinfunction "S_3") (pintype "passive"))
      (node (ref "R12") (pin "2") (pinfunction "2_2") (pintype "passive"))
    )
    (net (code "38") (name "Net-(Q13-PadE)") (class "Default")
      (node (ref "Q13") (pin "E") (pinfunction "E_E") (pintype "passive"))
      (node (ref "R5") (pin "2") (pinfunction "2_2") (pintype "passive"))
    )
    (net (code "39") (name "Net-(Q14-PadE)") (class "Default")
      (node (ref "Q14") (pin "E") (pinfunction "E_E") (pintype "passive"))
      (node (ref "R2") (pin "1") (pinfunction "1_1") (pintype "passive"))
    )
    (net (code "40") (name "Net-(U$1-EN)") (class "Default")
      (node (ref "B1") (pin "+") (pinfunction "+_+") (pintype "passive"))
      (node (ref "C2") (pin "1") (pinfunction "1_1") (pintype "passive"))
      (node (ref "C35") (pin "+") (pinfunction "+_+") (pintype "passive"))
      (node (ref "C36") (pin "1") (pinfunction "1_1") (pintype "passive"))
      (node (ref "C39") (pin "+") (pinfunction "+_+") (pintype "passive"))
      (node (ref "U$1") (pin "1") (pinfunction "IN_1") (pintype "bidirectional"))
      (node (ref "U$1") (pin "2") (pinfunction "IN_2") (pintype "bidirectional"))
      (node (ref "U$1") (pin "3") (pinfunction "IN_3") (pintype "bidirectional"))
      (node (ref "U$1") (pin "4") (pinfunction "EN_4") (pintype "bidirectional"))
      (node (ref "U$1") (pin "7") (pinfunction "PGFB_7") (pintype "bidirectional"))
    )
    (net (code "41") (name "Net-(U$1-ILIM)") (class "Default")
      (node (ref "R18") (pin "2") (pinfunction "2_2") (pintype "passive"))
      (node (ref "U$1") (pin "6") (pinfunction "ILIM_6") (pintype "bidirectional"))
    )
    (net (code "42") (name "Net-(U$1-OUTS)") (class "Default")
      (node (ref "U$1") (pin "10") (pinfunction "OUTS_10") (pintype "bidirectional"))
      (node (ref "U$2") (pin "3") (pinfunction "1_3") (pintype "passive"))
    )
    (net (code "43") (name "Net-(U$1-SET)") (class "Default")
      (node (ref "C1") (pin "1") (pinfunction "1_1") (pintype "passive"))
      (node (ref "R17") (pin "2") (pinfunction "2_2") (pintype "passive"))
      (node (ref "U$1") (pin "8") (pinfunction "SET_8") (pintype "bidirectional"))
    )
    (net (code "44") (name "Net-(U$2B-1)") (class "Default")
      (node (ref "C29") (pin "1") (pinfunction "1_1") (pintype "passive"))
      (node (ref "C34") (pin "+") (pinfunction "+_+") (pintype "passive"))
      (node (ref "C37") (pin "1") (pinfunction "1_1") (pintype "passive"))
      (node (ref "C42") (pin "+") (pinfunction "+_+") (pintype "passive"))
      (node (ref "JP1") (pin "2") (pinfunction "2_2") (pintype "passive"))
      (node (ref "U$1") (pin "11") (pinfunction "OUT_11") (pintype "bidirectional"))
      (node (ref "U$1") (pin "12") (pinfunction "OUT_12") (pintype "bidirectional"))
      (node (ref "U$2") (pin "4") (pinfunction "1_4") (pintype "passive"))
      (node (ref "X9") (pin "2") (pinfunction "KL_2") (pintype "passive"))
    )
    (net (code "45") (name "Net-(U$2B-2)") (class "Default")
      (node (ref "C1") (pin "2") (pinfunction "2_2") (pintype "passive"))
      (node (ref "R17") (pin "1") (pinfunction "1_1") (pintype "passive"))
      (node (ref "U$2") (pin "6") (pinfunction "2_6") (pintype "passive"))
    )
    (net (code "46") (name "Net-(U$5-EN)") (class "Default")
      (node (ref "B3") (pin "+") (pinfunction "+_+") (pintype "passive"))
      (node (ref "C38") (pin "+") (pinfunction "+_+") (pintype "passive"))
      (node (ref "C45") (pin "+") (pinfunction "+_+") (pintype "passive"))
      (node (ref "C47") (pin "1") (pinfunction "1_1") (pintype "passive"))
      (node (ref "C50") (pin "1") (pinfunction "1_1") (pintype "passive"))
      (node (ref "U$5") (pin "1") (pinfunction "IN_1") (pintype "bidirectional"))
      (node (ref "U$5") (pin "2") (pinfunction "IN_2") (pintype "bidirectional"))
      (node (ref "U$5") (pin "3") (pinfunction "IN_3") (pintype "bidirectional"))
      (node (ref "U$5") (pin "4") (pinfunction "EN_4") (pintype "bidirectional"))
      (node (ref "U$5") (pin "7") (pinfunction "PGFB_7") (pintype "bidirectional"))
    )
    (net (code "47") (name "Net-(U$5-ILIM)") (class "Default")
      (node (ref "R26") (pin "2") (pinfunction "2_2") (pintype "passive"))
      (node (ref "U$5") (pin "6") (pinfunction "ILIM_6") (pintype "bidirectional"))
    )
    (net (code "48") (name "Net-(U$5-OUTS)") (class "Default")
      (node (ref "U$5") (pin "10") (pinfunction "OUTS_10") (pintype "bidirectional"))
      (node (ref "U$6") (pin "3") (pinfunction "1_3") (pintype "passive"))
    )
    (net (code "49") (name "Net-(U$5-SET)") (class "Default")
      (node (ref "C46") (pin "1") (pinfunction "1_1") (pintype "passive"))
      (node (ref "R25") (pin "2") (pinfunction "2_2") (pintype "passive"))
      (node (ref "U$5") (pin "8") (pinfunction "SET_8") (pintype "bidirectional"))
    )
    (net (code "50") (name "Net-(U$6B-2)") (class "Default")
      (node (ref "C46") (pin "2") (pinfunction "2_2") (pintype "passive"))
      (node (ref "R25") (pin "1") (pinfunction "1_1") (pintype "passive"))
      (node (ref "U$6") (pin "6") (pinfunction "2_6") (pintype "passive"))
    )
    (net (code "51") (name "Net-(U$9-EN)") (class "Default")
      (node (ref "B5") (pin "+") (pinfunction "+_+") (pintype "passive"))
      (node (ref "C40") (pin "+") (pinfunction "+_+") (pintype "passive"))
      (node (ref "C59") (pin "+") (pinfunction "+_+") (pintype "passive"))
      (node (ref "C61") (pin "1") (pinfunction "1_1") (pintype "passive"))
      (node (ref "C64") (pin "1") (pinfunction "1_1") (pintype "passive"))
      (node (ref "U$9") (pin "1") (pinfunction "IN_1") (pintype "bidirectional"))
      (node (ref "U$9") (pin "2") (pinfunction "IN_2") (pintype "bidirectional"))
      (node (ref "U$9") (pin "3") (pinfunction "IN_3") (pintype "bidirectional"))
      (node (ref "U$9") (pin "4") (pinfunction "EN_4") (pintype "bidirectional"))
      (node (ref "U$9") (pin "7") (pinfunction "PGFB_7") (pintype "bidirectional"))
    )
    (net (code "52") (name "Net-(U$9-ILIM)") (class "Default")
      (node (ref "R30") (pin "2") (pinfunction "2_2") (pintype "passive"))
      (node (ref "U$9") (pin "6") (pinfunction "ILIM_6") (pintype "bidirectional"))
    )
    (net (code "53") (name "Net-(U$9-SET)") (class "Default")
      (node (ref "C60") (pin "1") (pinfunction "1_1") (pintype "passive"))
      (node (ref "R29") (pin "2") (pinfunction "2_2") (pintype "passive"))
      (node (ref "U$9") (pin "8") (pinfunction "SET_8") (pintype "bidirectional"))
    )
    (net (code "54") (name "Net-(U$10A-1)") (class "Default")
      (node (ref "U$10") (pin "3") (pinfunction "1_3") (pintype "passive"))
      (node (ref "U$9") (pin "10") (pinfunction "OUTS_10") (pintype "bidirectional"))
    )
    (net (code "55") (name "Net-(U$10B-2)") (class "Default")
      (node (ref "C60") (pin "2") (pinfunction "2_2") (pintype "passive"))
      (node (ref "R29") (pin "1") (pinfunction "1_1") (pintype "passive"))
      (node (ref "U$10") (pin "6") (pinfunction "2_6") (pintype "passive"))
    )
    (net (code "56") (name "Net-(X5A-KL)") (class "Default")
      (node (ref "D15") (pin "A") (pinfunction "A_A") (pintype "passive"))
      (node (ref "R13") (pin "1") (pinfunction "1_1") (pintype "passive"))
      (node (ref "X5") (pin "1") (pinfunction "KL_1") (pintype "passive"))
    )
    (net (code "57") (name "Net-(X6B-KL)") (class "Default")
      (node (ref "C26") (pin "1") (pinfunction "1_1") (pintype "passive"))
      (node (ref "C28") (pin "2") (pinfunction "2_2") (pintype "passive"))
      (node (ref "D17") (pin "A") (pinfunction "A_A") (pintype "passive"))
      (node (ref "D19") (pin "C") (pinfunction "C_C") (pintype "passive"))
      (node (ref "X6") (pin "2") (pinfunction "KL_2") (pintype "passive"))
    )
    (net (code "58") (name "Net-(X7A-KL)") (class "Default")
      (node (ref "C25") (pin "1") (pinfunction "1_1") (pintype "passive"))
      (node (ref "C27") (pin "2") (pinfunction "2_2") (pintype "passive"))
      (node (ref "D16") (pin "A") (pinfunction "A_A") (pintype "passive"))
      (node (ref "D18") (pin "C") (pinfunction "C_C") (pintype "passive"))
      (node (ref "X7") (pin "1") (pinfunction "KL_1") (pintype "passive"))
    )
    (net (code "59") (name "Net-(X8A-KL)") (class "Default")
      (node (ref "B1") (pin "AC2") (pinfunction "AC2_AC2") (pintype "passive"))
      (node (ref "X8") (pin "1") (pinfunction "KL_1") (pintype "passive"))
    )
    (net (code "60") (name "Net-(X8B-KL)") (class "Default")
      (node (ref "B1") (pin "AC1") (pinfunction "AC1_AC1") (pintype "passive"))
      (node (ref "X8") (pin "2") (pinfunction "KL_2") (pintype "passive"))
    )
    (net (code "61") (name "Net-(X12A-KL)") (class "Default")
      (node (ref "B3") (pin "AC2") (pinfunction "AC2_AC2") (pintype "passive"))
      (node (ref "X12") (pin "1") (pinfunction "KL_1") (pintype "passive"))
    )
    (net (code "62") (name "Net-(X12B-KL)") (class "Default")
      (node (ref "B3") (pin "AC1") (pinfunction "AC1_AC1") (pintype "passive"))
      (node (ref "X12") (pin "2") (pinfunction "KL_2") (pintype "passive"))
    )
    (net (code "63") (name "Net-(X16A-KL)") (class "Default")
      (node (ref "B5") (pin "AC2") (pinfunction "AC2_AC2") (pintype "passive"))
      (node (ref "X16") (pin "1") (pinfunction "KL_1") (pintype "passive"))
    )
    (net (code "64") (name "Net-(X16B-KL)") (class "Default")
      (node (ref "B5") (pin "AC1") (pinfunction "AC1_AC1") (pintype "passive"))
      (node (ref "X16") (pin "2") (pinfunction "KL_2") (pintype "passive"))
    )
    (net (code "65") (name "V+") (class "Default")
      (node (ref "C16") (pin "+") (pinfunction "+_+") (pintype "passive"))
      (node (ref "C18") (pin "2") (pinfunction "2_2") (pintype "passive"))
      (node (ref "C20") (pin "2") (pinfunction "2_2") (pintype "passive"))
      (node (ref "C24") (pin "1") (pinfunction "1_1") (pintype "passive"))
      (node (ref "C6") (pin "+") (pinfunction "+_+") (pintype "passive"))
      (node (ref "D11") (pin "A") (pinfunction "A_A") (pintype "passive"))
      (node (ref "IC1") (pin "7") (pinfunction "V+_7") (pintype "power_in"))
      (node (ref "Q4") (pin "E") (pinfunction "E_E") (pintype "passive"))
      (node (ref "Q8") (pin "1") (pinfunction "D_1") (pintype "passive"))
      (node (ref "R13") (pin "2") (pinfunction "2_2") (pintype "passive"))
      (node (ref "R8") (pin "2") (pinfunction "2_2") (pintype "passive"))
      (node (ref "X1") (pin "1") (pinfunction "KL_1") (pintype "passive"))
      (node (ref "X2") (pin "1") (pinfunction "KL_1") (pintype "passive"))
      (node (ref "X3") (pin "1") (pinfunction "KL_1") (pintype "passive"))
      (node (ref "X4") (pin "1") (pinfunction "KL_1") (pintype "passive"))
    )
    (net (code "66") (name "V-") (class "Default")
      (node (ref "C10") (pin "-") (pinfunction "-_-") (pintype "passive"))
      (node (ref "C17") (pin "1") (pinfunction "1_1") (pintype "passive"))
      (node (ref "C19") (pin "1") (pinfunction "1_1") (pintype "passive"))
      (node (ref "C21") (pin "2") (pinfunction "2_2") (pintype "passive"))
      (node (ref "C3") (pin "-") (pinfunction "-_-") (pintype "passive"))
      (node (ref "D10") (pin "C") (pinfunction "C_C") (pintype "passive"))
      (node (ref "IC2") (pin "4") (pinfunction "V-_4") (pintype "power_in"))
      (node (ref "Q12") (pin "2") (pinfunction "G_2") (pintype "passive"))
      (node (ref "Q7") (pin "E") (pinfunction "E_E") (pintype "passive"))
      (node (ref "R12") (pin "1") (pinfunction "1_1") (pintype "passive"))
      (node (ref "R14") (pin "1") (pinfunction "1_1") (pintype "passive"))
      (node (ref "R9") (pin "1") (pinfunction "1_1") (pintype "passive"))
      (node (ref "X1") (pin "3") (pinfunction "KL_3") (pintype "passive"))
      (node (ref "X2") (pin "3") (pinfunction "KL_3") (pintype "passive"))
      (node (ref "X3") (pin "3") (pinfunction "KL_3") (pintype "passive"))
      (node (ref "X4") (pin "3") (pinfunction "KL_3") (pintype "passive"))
    )
    (net (code "67") (name "unconnected-(IC1-TRIM1-Pad1)") (class "Default")
      (node (ref "IC1") (pin "1") (pinfunction "TRIM1_1") (pintype "passive"))
    )
    (net (code "68") (name "unconnected-(IC1-TRIM2-Pad8)") (class "Default")
      (node (ref "IC1") (pin "8") (pinfunction "TRIM2_8") (pintype "passive"))
    )
    (net (code "69") (name "unconnected-(IC2-TRIM1-Pad1)") (class "Default")
      (node (ref "IC2") (pin "1") (pinfunction "TRIM1_1") (pintype "passive"))
    )
    (net (code "70") (name "unconnected-(IC2-TRIM2-Pad8)") (class "Default")
      (node (ref "IC2") (pin "8") (pinfunction "TRIM2_8") (pintype "passive"))
    )
    (net (code "71") (name "unconnected-(U$1-PG-Pad5)") (class "Default")
      (node (ref "U$1") (pin "5") (pinfunction "PG_5") (pintype "bidirectional"))
    )
    (net (code "72") (name "unconnected-(U$5-PG-Pad5)") (class "Default")
      (node (ref "U$5") (pin "5") (pinfunction "PG_5") (pintype "bidirectional"))
    )
    (net (code "73") (name "unconnected-(U$9-PG-Pad5)") (class "Default")
      (node (ref "U$9") (pin "5") (pinfunction "PG_5") (pintype "bidirectional"))
    )
  )
)
